# Wiring-Board-Nano_v2.net
KiCad netlist of a schematic drawn in EAGLE
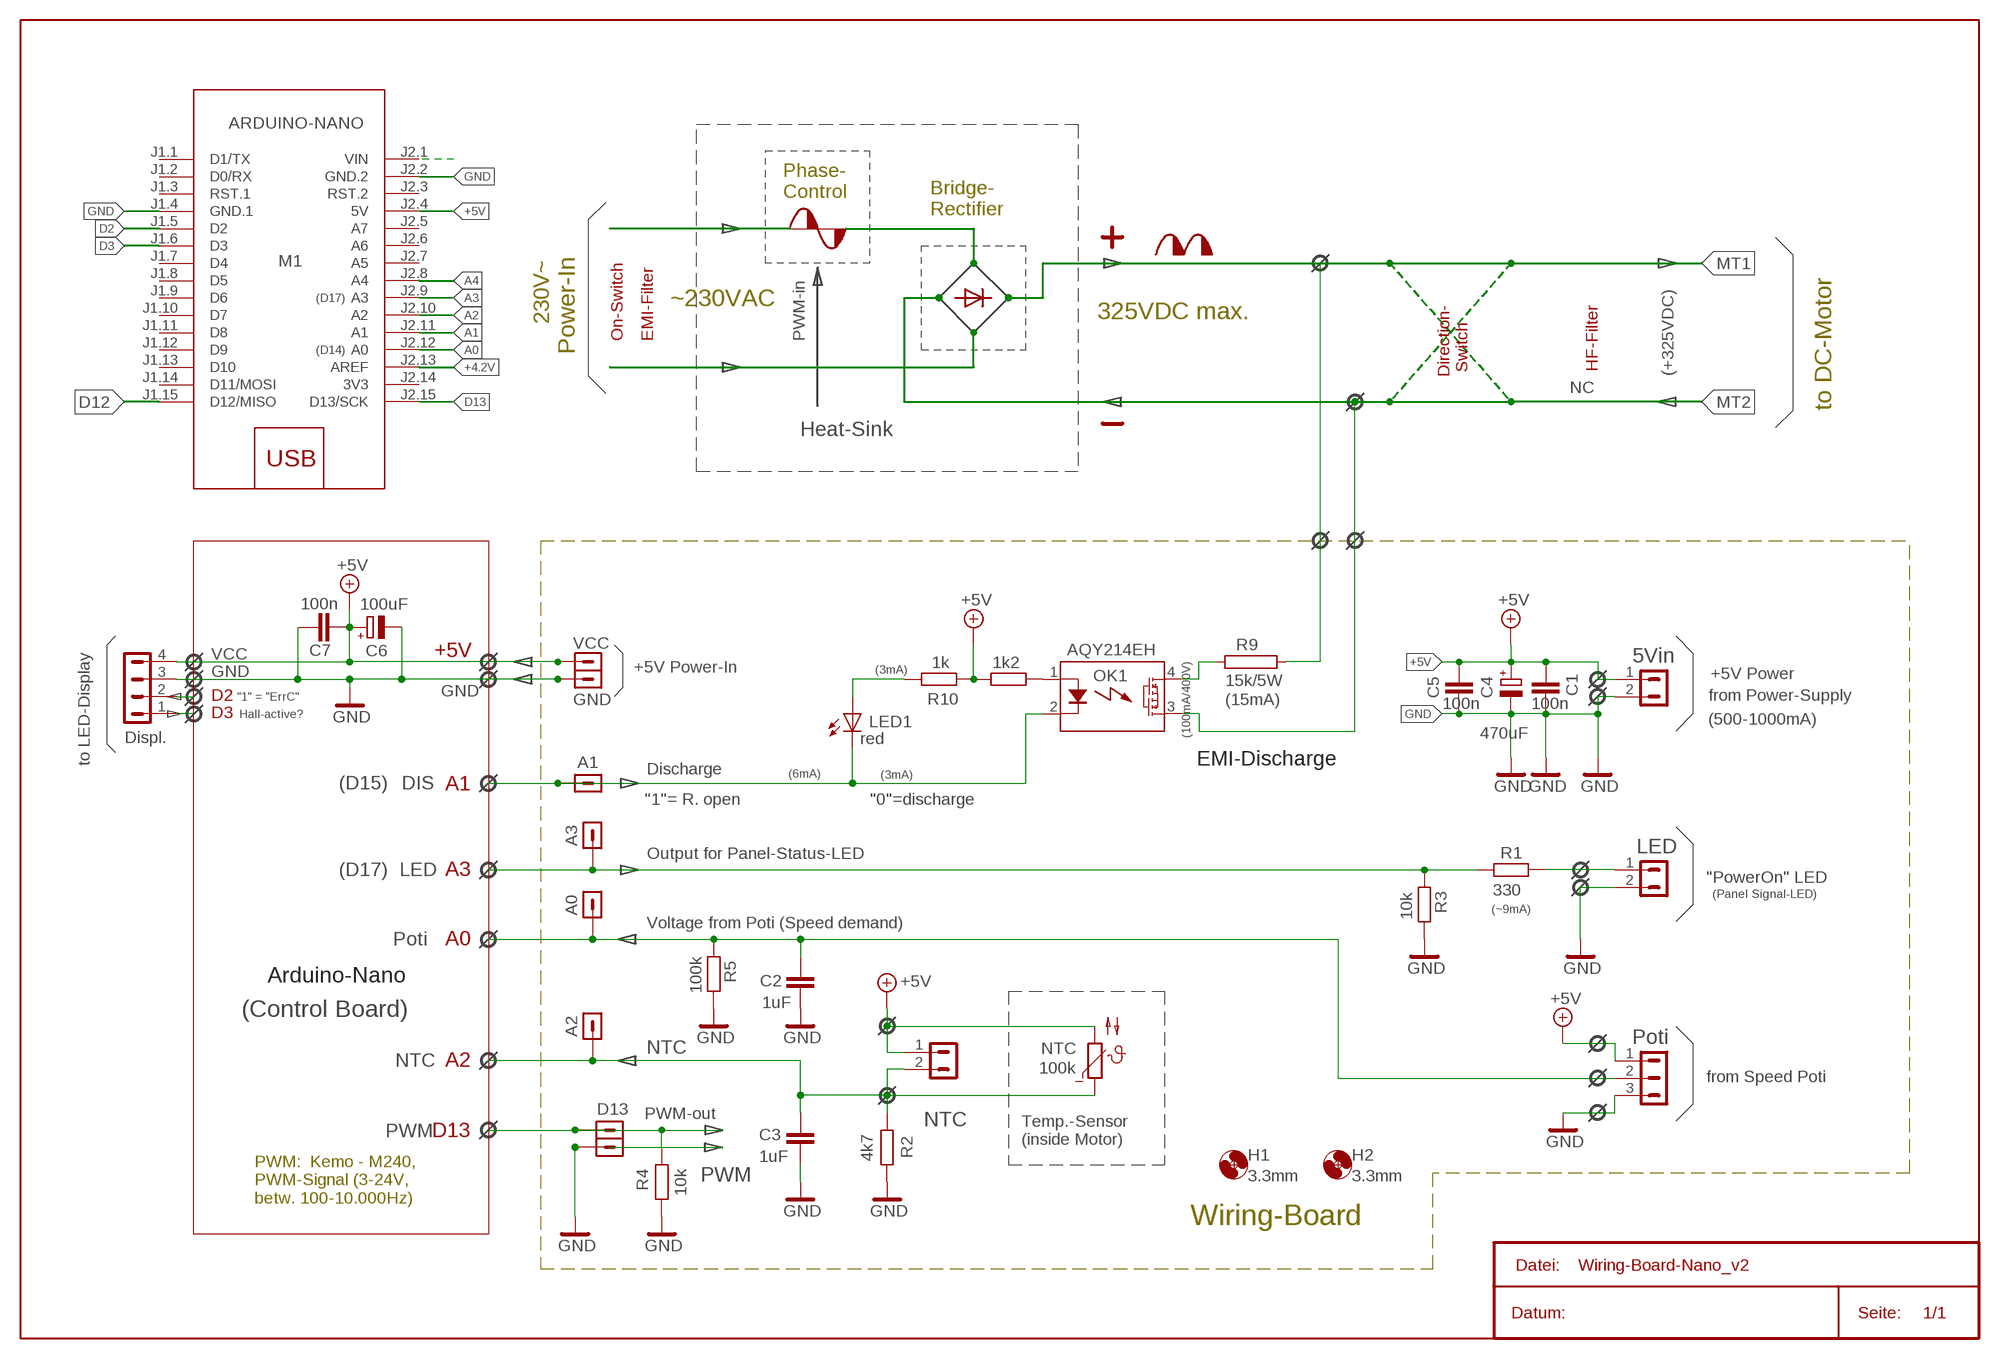
[diagram p0: schematic, sheet 1]

(export (version "E")
  (design (tool "Eeschema 10.0.6"))
  (components
    (comp (ref "C1")
      (value "100n")
      (footprint "eagle-import:C0805")
      (libsource (lib "eagle-import") (part "C-EUC0805"))
    )
    (comp (ref "C2")
      (value "1uF")
      (footprint "eagle-import:C0805")
      (libsource (lib "eagle-import") (part "C-EUC0805"))
    )
    (comp (ref "C3")
      (value "1uF")
      (footprint "eagle-import:C0805")
      (libsource (lib "eagle-import") (part "C-EUC0805"))
    )
    (comp (ref "C4")
      (value "470uF")
      (footprint "eagle-import:E3,5-8")
      (libsource (lib "eagle-import") (part "CPOL-EUE3.5-8"))
    )
    (comp (ref "C5")
      (value "100n")
      (footprint "eagle-import:C0805")
      (libsource (lib "eagle-import") (part "C-EUC0805"))
    )
    (comp (ref "C6")
      (value "100uF")
      (footprint "eagle-import:E2,5-7")
      (libsource (lib "eagle-import") (part "CPOL-EUE2.5-7"))
    )
    (comp (ref "C7")
      (value "100n")
      (footprint "eagle-import:C0805")
      (libsource (lib "eagle-import") (part "C-EUC0805"))
    )
    (comp (ref "H1")
      (value "3.3mm")
      (footprint "eagle-import:3,3")
      (libsource (lib "eagle-import") (part "MOUNT-HOLE3.3"))
    )
    (comp (ref "H2")
      (value "3.3mm")
      (footprint "eagle-import:3,3")
      (libsource (lib "eagle-import") (part "MOUNT-HOLE3.3"))
    )
    (comp (ref "LED1")
      (value "red")
      (footprint "eagle-import:CHIPLED_0805")
      (libsource (lib "eagle-import") (part "LEDCHIPLED_0805"))
    )
    (comp (ref "M1")
      (value "ARDUINO-NANO")
      (footprint "eagle-import:ARDUINO-NANO-3.0")
      (libsource (lib "eagle-import") (part "ARDUINO-NANO-3.0"))
    )
    (comp (ref "OK1")
      (value "AQY214EH")
      (footprint "eagle-import:GULLWING")
      (libsource (lib "eagle-import") (part "AQY"))
    )
    (comp (ref "R1")
      (value "330")
      (footprint "eagle-import:R0805")
      (libsource (lib "eagle-import") (part "R-EU_R0805"))
    )
    (comp (ref "R2")
      (value "4k7")
      (footprint "eagle-import:R0805")
      (libsource (lib "eagle-import") (part "R-EU_R0805"))
    )
    (comp (ref "R3")
      (value "10k")
      (footprint "eagle-import:R0805")
      (libsource (lib "eagle-import") (part "R-EU_R0805"))
    )
    (comp (ref "R4")
      (value "10k")
      (footprint "eagle-import:R0805")
      (libsource (lib "eagle-import") (part "R-EU_R0805"))
    )
    (comp (ref "R5")
      (value "100k")
      (footprint "eagle-import:R0805")
      (libsource (lib "eagle-import") (part "R-EU_R0805"))
    )
    (comp (ref "R9")
      (value "15k/5W")
      (footprint "eagle-import:KH206-8")
      (libsource (lib "eagle-import") (part "RKH206-8"))
    )
    (comp (ref "R10")
      (value "1k")
      (footprint "eagle-import:R0805")
      (libsource (lib "eagle-import") (part "R-EU_R0805"))
    )
    (comp (ref "R11")
      (value "1k2")
      (footprint "eagle-import:R0805")
      (libsource (lib "eagle-import") (part "R-EU_R0805"))
    )
    (comp (ref "SV1")
      (value "5Vin")
      (footprint "eagle-import:MA02-1")
      (libsource (lib "eagle-import") (part "MA02-10"))
    )
    (comp (ref "SV2")
      (value "LED")
      (footprint "eagle-import:MA02-1")
      (libsource (lib "eagle-import") (part "MA02-10"))
    )
    (comp (ref "SV3")
      (value "Poti")
      (footprint "eagle-import:MA03-1")
      (libsource (lib "eagle-import") (part "MA03-10"))
    )
    (comp (ref "SV4")
      (value "NTC")
      (footprint "eagle-import:MA02-1")
      (libsource (lib "eagle-import") (part "MA02-10"))
    )
    (comp (ref "SV6")
      (value "Displ.")
      (footprint "eagle-import:MA04-1")
      (libsource (lib "eagle-import") (part "MA04-10"))
    )
  )
  (nets
    (net (code "1") (name "+4.2V") (class "Default")
      (node (ref "M1") (pin "J2.13") (pinfunction "AREF_J2.13") (pintype "bidirectional"))
    )
    (net (code "2") (name "+5V") (class "Default")
      (node (ref "C1") (pin "1") (pinfunction "1_1") (pintype "passive"))
      (node (ref "C4") (pin "+") (pinfunction "+_+") (pintype "passive"))
      (node (ref "C5") (pin "1") (pinfunction "1_1") (pintype "passive"))
      (node (ref "C6") (pin "+") (pinfunction "+_+") (pintype "passive"))
      (node (ref "C7") (pin "1") (pinfunction "1_1") (pintype "passive"))
      (node (ref "M1") (pin "J2.4") (pinfunction "5V_J2.4") (pintype "power_in"))
      (node (ref "R10") (pin "2") (pinfunction "2_2") (pintype "passive"))
      (node (ref "R11") (pin "1") (pinfunction "1_1") (pintype "passive"))
      (node (ref "SV1") (pin "1") (pinfunction "1_1") (pintype "passive"))
      (node (ref "SV3") (pin "1") (pinfunction "1_1") (pintype "passive"))
      (node (ref "SV4") (pin "1") (pinfunction "1_1") (pintype "passive"))
      (node (ref "SV6") (pin "4") (pinfunction "4_4") (pintype "passive"))
    )
    (net (code "3") (name "/3V3") (class "Default")
      (node (ref "M1") (pin "J2.14") (pinfunction "3V3_J2.14") (pintype "power_in"))
    )
    (net (code "4") (name "/PLUS") (class "Default")
      (node (ref "R9") (pin "2") (pinfunction "2_2") (pintype "passive"))
    )
    (net (code "5") (name "A0") (class "Default")
      (node (ref "C2") (pin "1") (pinfunction "1_1") (pintype "passive"))
      (node (ref "M1") (pin "J2.12") (pinfunction "A0_J2.12") (pintype "bidirectional"))
      (node (ref "R5") (pin "1") (pinfunction "1_1") (pintype "passive"))
      (node (ref "SV3") (pin "2") (pinfunction "2_2") (pintype "passive"))
    )
    (net (code "6") (name "A1") (class "Default")
      (node (ref "LED1") (pin "C") (pinfunction "C_C") (pintype "passive"))
      (node (ref "M1") (pin "J2.11") (pinfunction "A1_J2.11") (pintype "bidirectional"))
      (node (ref "OK1") (pin "2") (pinfunction "K_2") (pintype "passive"))
    )
    (net (code "7") (name "A2") (class "Default")
      (node (ref "C3") (pin "1") (pinfunction "1_1") (pintype "passive"))
      (node (ref "M1") (pin "J2.10") (pinfunction "A2_J2.10") (pintype "bidirectional"))
      (node (ref "R2") (pin "2") (pinfunction "2_2") (pintype "passive"))
      (node (ref "SV4") (pin "2") (pinfunction "2_2") (pintype "passive"))
    )
    (net (code "8") (name "A3") (class "Default")
      (node (ref "M1") (pin "J2.9") (pinfunction "A3_J2.9") (pintype "bidirectional"))
      (node (ref "R1") (pin "1") (pinfunction "1_1") (pintype "passive"))
      (node (ref "R3") (pin "1") (pinfunction "1_1") (pintype "passive"))
    )
    (net (code "9") (name "A4") (class "Default")
      (node (ref "M1") (pin "J2.8") (pinfunction "A4_J2.8") (pintype "bidirectional"))
    )
    (net (code "10") (name "D2") (class "Default")
      (node (ref "M1") (pin "J1.5") (pinfunction "D2_J1.5") (pintype "bidirectional"))
      (node (ref "SV6") (pin "2") (pinfunction "2_2") (pintype "passive"))
    )
    (net (code "11") (name "D3") (class "Default")
      (node (ref "M1") (pin "J1.6") (pinfunction "D3_J1.6") (pintype "bidirectional"))
      (node (ref "SV6") (pin "1") (pinfunction "1_1") (pintype "passive"))
    )
    (net (code "12") (name "D12") (class "Default")
      (node (ref "M1") (pin "J1.15") (pinfunction "D12/MISO_J1.15") (pintype "bidirectional"))
    )
    (net (code "13") (name "D13") (class "Default")
      (node (ref "M1") (pin "J2.15") (pinfunction "D13/SCK_J2.15") (pintype "bidirectional"))
      (node (ref "R4") (pin "1") (pinfunction "1_1") (pintype "passive"))
    )
    (net (code "14") (name "GND") (class "Default")
      (node (ref "C1") (pin "2") (pinfunction "2_2") (pintype "passive"))
      (node (ref "C2") (pin "2") (pinfunction "2_2") (pintype "passive"))
      (node (ref "C3") (pin "2") (pinfunction "2_2") (pintype "passive"))
      (node (ref "C4") (pin "-") (pinfunction "-_-") (pintype "passive"))
      (node (ref "C5") (pin "2") (pinfunction "2_2") (pintype "passive"))
      (node (ref "C6") (pin "-") (pinfunction "-_-") (pintype "passive"))
      (node (ref "C7") (pin "2") (pinfunction "2_2") (pintype "passive"))
      (node (ref "M1") (pin "J1.4") (pinfunction "GND.1_J1.4") (pintype "power_in"))
      (node (ref "M1") (pin "J2.2") (pinfunction "GND.2_J2.2") (pintype "power_in"))
      (node (ref "R2") (pin "1") (pinfunction "1_1") (pintype "passive"))
      (node (ref "R3") (pin "2") (pinfunction "2_2") (pintype "passive"))
      (node (ref "R4") (pin "2") (pinfunction "2_2") (pintype "passive"))
      (node (ref "R5") (pin "2") (pinfunction "2_2") (pintype "passive"))
      (node (ref "SV1") (pin "2") (pinfunction "2_2") (pintype "passive"))
      (node (ref "SV2") (pin "2") (pinfunction "2_2") (pintype "passive"))
      (node (ref "SV3") (pin "3") (pinfunction "3_3") (pintype "passive"))
      (node (ref "SV6") (pin "3") (pinfunction "3_3") (pintype "passive"))
    )
    (net (code "17") (name "Net-(LED1-PadA)") (class "Default")
      (node (ref "LED1") (pin "A") (pinfunction "A_A") (pintype "passive"))
      (node (ref "R10") (pin "1") (pinfunction "1_1") (pintype "passive"))
    )
    (net (code "18") (name "Net-(OK1-A)") (class "Default")
      (node (ref "OK1") (pin "1") (pinfunction "A_1") (pintype "passive"))
      (node (ref "R11") (pin "2") (pinfunction "2_2") (pintype "passive"))
    )
    (net (code "19") (name "Net-(OK1-DS1)") (class "Default")
      (node (ref "OK1") (pin "4") (pinfunction "DS1_4") (pintype "passive"))
      (node (ref "R9") (pin "1") (pinfunction "1_1") (pintype "passive"))
    )
    (net (code "20") (name "Net-(R1-Pad2)") (class "Default")
      (node (ref "R1") (pin "2") (pinfunction "2_2") (pintype "passive"))
      (node (ref "SV2") (pin "1") (pinfunction "1_1") (pintype "passive"))
    )
    (net (code "21") (name "unconnected-(M1-A5-PadJ2.7)") (class "Default")
      (node (ref "M1") (pin "J2.7") (pinfunction "A5_J2.7") (pintype "bidirectional"))
    )
    (net (code "22") (name "unconnected-(M1-A6-PadJ2.6)") (class "Default")
      (node (ref "M1") (pin "J2.6") (pinfunction "A6_J2.6") (pintype "bidirectional"))
    )
    (net (code "23") (name "unconnected-(M1-A7-PadJ2.5)") (class "Default")
      (node (ref "M1") (pin "J2.5") (pinfunction "A7_J2.5") (pintype "bidirectional"))
    )
    (net (code "24") (name "unconnected-(M1-D0{slash}RX-PadJ1.2)") (class "Default")
      (node (ref "M1") (pin "J1.2") (pinfunction "D0/RX_J1.2") (pintype "bidirectional"))
    )
    (net (code "25") (name "unconnected-(M1-D1{slash}TX-PadJ1.1)") (class "Default")
      (node (ref "M1") (pin "J1.1") (pinfunction "D1/TX_J1.1") (pintype "bidirectional"))
    )
    (net (code "26") (name "unconnected-(M1-D4-PadJ1.7)") (class "Default")
      (node (ref "M1") (pin "J1.7") (pinfunction "D4_J1.7") (pintype "bidirectional"))
    )
    (net (code "27") (name "unconnected-(M1-D5-PadJ1.8)") (class "Default")
      (node (ref "M1") (pin "J1.8") (pinfunction "D5_J1.8") (pintype "bidirectional"))
    )
    (net (code "28") (name "unconnected-(M1-D6-PadJ1.9)") (class "Default")
      (node (ref "M1") (pin "J1.9") (pinfunction "D6_J1.9") (pintype "bidirectional"))
    )
    (net (code "29") (name "unconnected-(M1-D7-PadJ1.10)") (class "Default")
      (node (ref "M1") (pin "J1.10") (pinfunction "D7_J1.10") (pintype "bidirectional"))
    )
    (net (code "30") (name "unconnected-(M1-D8-PadJ1.11)") (class "Default")
      (node (ref "M1") (pin "J1.11") (pinfunction "D8_J1.11") (pintype "bidirectional"))
    )
    (net (code "31") (name "unconnected-(M1-D9-PadJ1.12)") (class "Default")
      (node (ref "M1") (pin "J1.12") (pinfunction "D9_J1.12") (pintype "bidirectional"))
    )
    (net (code "32") (name "unconnected-(M1-D10-PadJ1.13)") (class "Default")
      (node (ref "M1") (pin "J1.13") (pinfunction "D10_J1.13") (pintype "bidirectional"))
    )
    (net (code "33") (name "unconnected-(M1-D11{slash}MOSI-PadJ1.14)") (class "Default")
      (node (ref "M1") (pin "J1.14") (pinfunction "D11/MOSI_J1.14") (pintype "bidirectional"))
    )
    (net (code "34") (name "unconnected-(M1-RST.1-PadJ1.3)") (class "Default")
      (node (ref "M1") (pin "J1.3") (pinfunction "RST.1_J1.3") (pintype "bidirectional"))
    )
    (net (code "35") (name "unconnected-(M1-RST.2-PadJ2.3)") (class "Default")
      (node (ref "M1") (pin "J2.3") (pinfunction "RST.2_J2.3") (pintype "bidirectional"))
    )
    (net (code "36") (name "unconnected-(M1-VIN-PadJ2.1)") (class "Default")
      (node (ref "M1") (pin "J2.1") (pinfunction "VIN_J2.1") (pintype "power_in"))
    )
    (net (code "37") (name "unconnected-(OK1-DS2-Pad3)") (class "Default")
      (node (ref "OK1") (pin "3") (pinfunction "DS2_3") (pintype "passive"))
    )
  )
)
